# NNP-DWG-125-001-000_PG4_Schematic_Drawin.net
KiCad netlist of a schematic drawn in Altium Designer
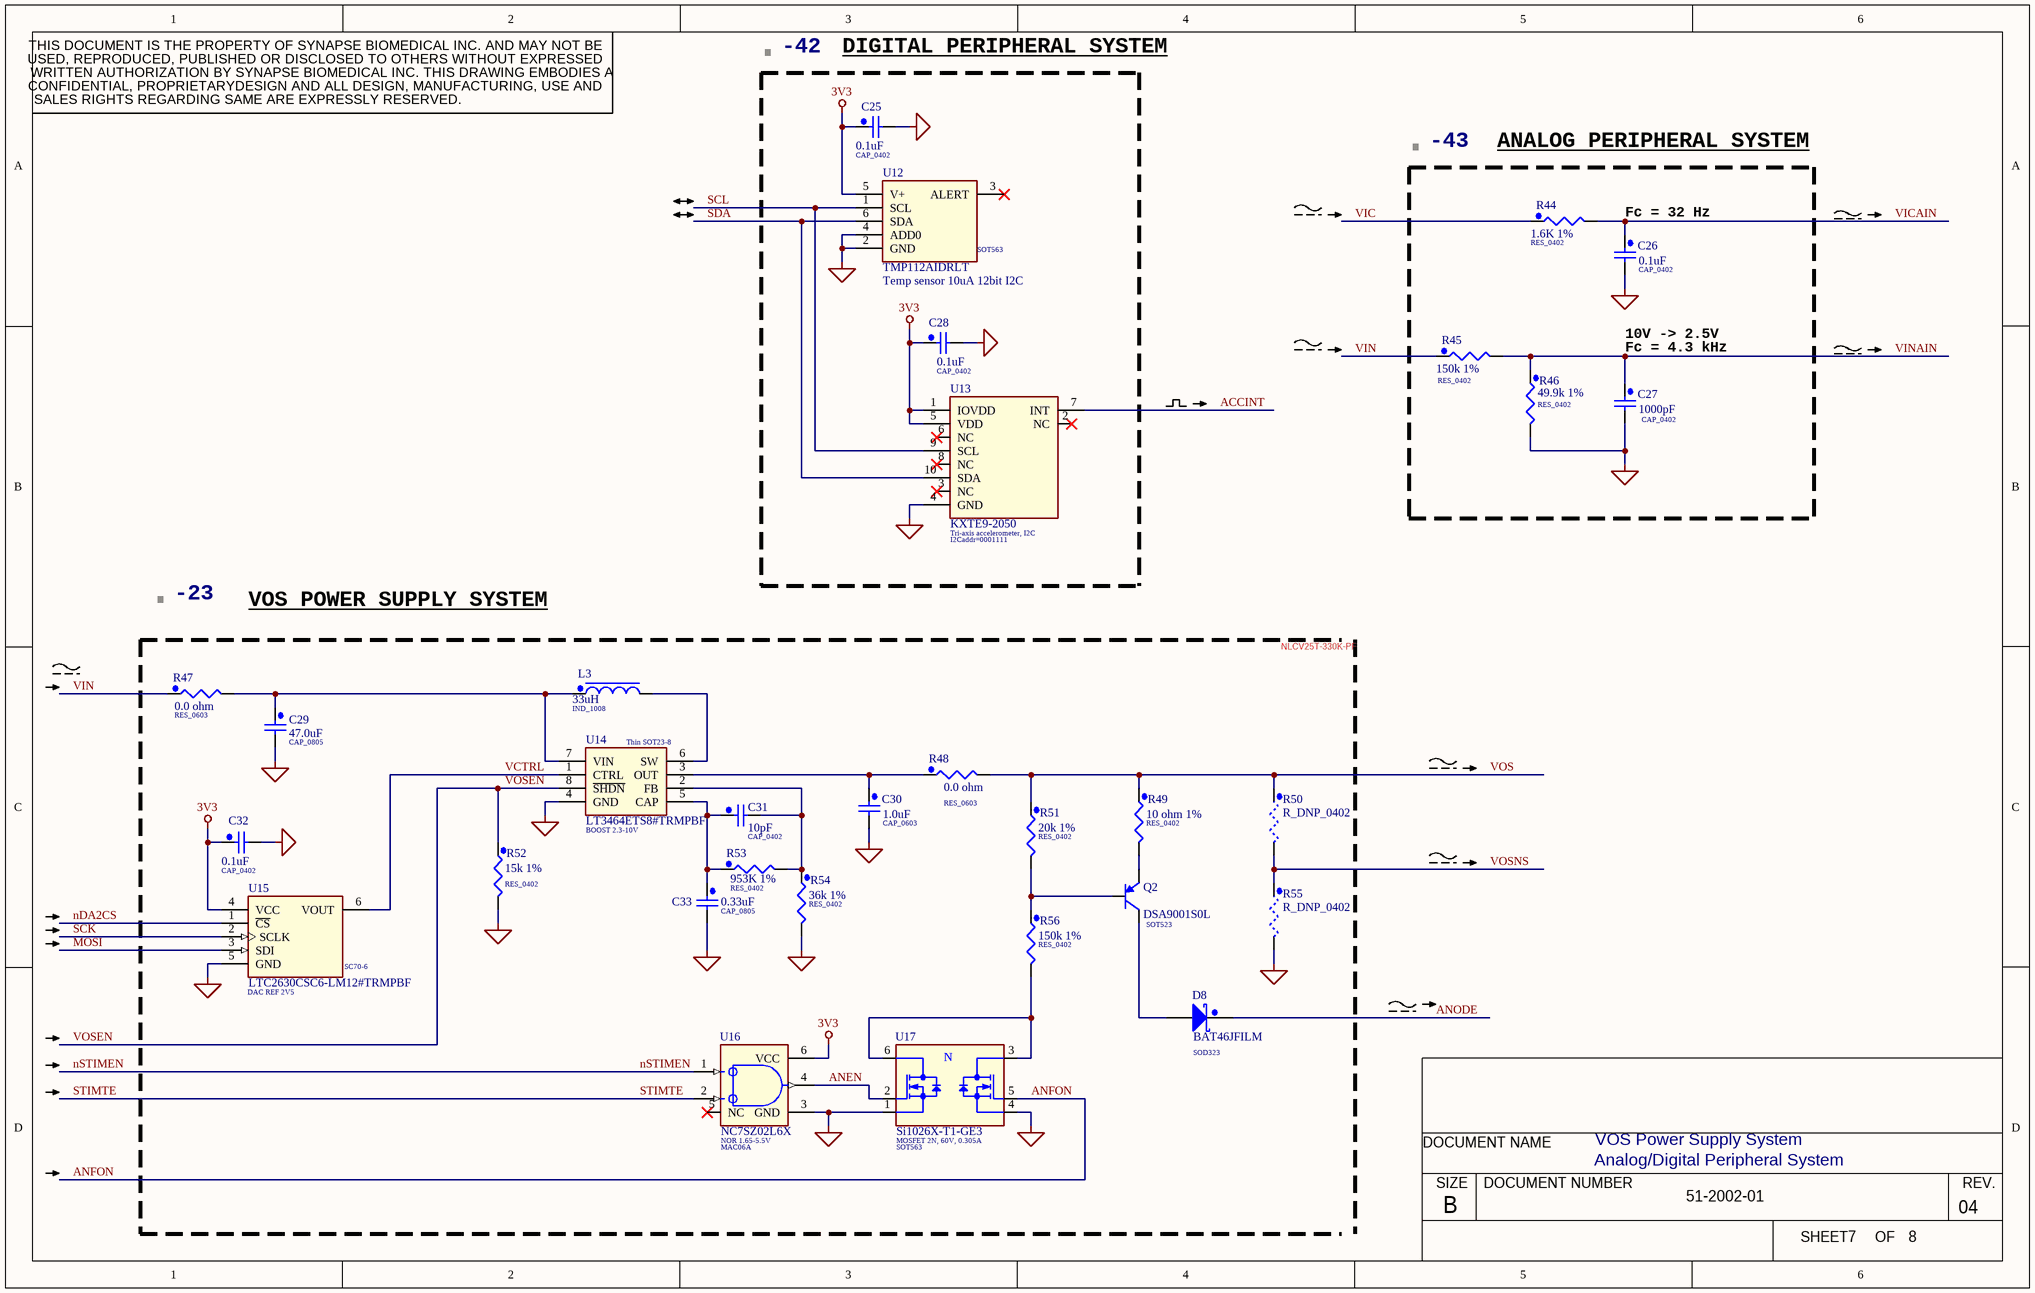
[diagram p0: NNP-DWG-125-001-000 PG4 Schematic Drawing Pg7.SchDoc]

(export (version "E")
  (design (tool "Eeschema 10.0.6"))
  (components
    (comp (ref "-23")
      (value "BOM_S1")
      (description "BOM item small graphic")
      (fields (field (name "XDESCRIPTION") "VOS POWER SUPPLY SYSTEM"))
      (libsource (lib "BOM_sym") (part "BOM_S1"))
    )
    (comp (ref "-42")
      (value "BOM_S1")
      (description "BOM item small graphic")
      (fields (field (name "XDESCRIPTION") "DIGITAL PERIPHERAL SYSTEM"))
      (libsource (lib "BOM_sym") (part "BOM_S1"))
    )
    (comp (ref "-43")
      (value "BOM_S1")
      (description "BOM item small graphic")
      (fields (field (name "XDESCRIPTION") "ANALOG PERIPHERAL SYSTEM"))
      (libsource (lib "BOM_sym") (part "BOM_S1"))
    )
    (comp (ref "C25")
      (value "0.1uF")
      (footprint "CAP_0402")
      (description "0.1uF, 16V, X7R, 0402, RoHS")
      (fields
        (field (name "MFR") "Murata Electronics North America")
        (field (name "PACKAGEDESCRIPTION") "CAP_0402")
        (field (name "MPN") "GRM155R71C104KA88D")
      )
      (libsource (lib "NNPS Integrated Parts") (part "GRM155R71C104KA88D"))
    )
    (comp (ref "C26")
      (value "0.1uF")
      (footprint "CAP_0402")
      (description "0.1uF, 16V, X7R, 0402, RoHS")
      (fields
        (field (name "MFR") "Murata Electronics North America")
        (field (name "PACKAGEDESCRIPTION") "CAP_0402")
        (field (name "MPN") "GRM155R71C104KA88D")
      )
      (libsource (lib "NNPS Integrated Parts") (part "GRM155R71C104KA88D"))
    )
    (comp (ref "C27")
      (value "1000pF")
      (footprint "CAP_0402")
      (description "1000pF, 50V, C0G, 5%, 0402, RoHS")
      (fields
        (field (name "MFR") "Murata Electronics North America")
        (field (name "PACKAGEDESCRIPTION") "CAP_0402")
        (field (name "MPN") "GRM1555C1H102JA01D")
      )
      (libsource (lib "NNPS Integrated Parts") (part "GRM1555C1H102JA01D"))
    )
    (comp (ref "C28")
      (value "0.1uF")
      (footprint "CAP_0402")
      (description "0.1uF, 16V, X7R, 0402, RoHS")
      (fields
        (field (name "MFR") "Murata Electronics North America")
        (field (name "PACKAGEDESCRIPTION") "CAP_0402")
        (field (name "MPN") "GRM155R71C104KA88D")
      )
      (libsource (lib "NNPS Integrated Parts") (part "GRM155R71C104KA88D"))
    )
    (comp (ref "C29")
      (value "47.0uF")
      (footprint "CAP_0805")
      (description "47uF, 10V, X5R, 20%, 0805, RoHS")
      (fields
        (field (name "MFR") "TDK Corporation")
        (field (name "PACKAGEDESCRIPTION") "CAP_0805")
        (field (name "MPN") "C2012X5R1A476M125AC")
      )
      (libsource (lib "NNPS Integrated Parts") (part "C2012X5R1A476M125AC"))
    )
    (comp (ref "C30")
      (value "1.0uF")
      (footprint "CAP_0603")
      (description "1uF, 50V, X5R, 10%, 0603, RoHS")
      (fields
        (field (name "MFR") "Murata Electronics North America")
        (field (name "PACKAGEDESCRIPTION") "CAP_0603")
        (field (name "MPN") "GRM188R61H105KAALD")
      )
      (libsource (lib "NNPS Integrated Parts") (part "UMK107BJ105KA-T"))
    )
    (comp (ref "C31")
      (value "10pF")
      (footprint "CAP_0402")
      (description "10pF, 50V, C0G, 5%, 0402, RoHS")
      (fields
        (field (name "MFR") "Murata Electronics North America")
        (field (name "PACKAGEDESCRIPTION") "CAP_0402")
        (field (name "MPN") "GRM1555C1H100JA01D")
      )
      (libsource (lib "NNPS Integrated Parts") (part "GRM1555C1H100JZ01"))
    )
    (comp (ref "C32")
      (value "0.1uF")
      (footprint "CAP_0402")
      (description "0.1uF, 16V, X7R, 0402, RoHS")
      (fields
        (field (name "MFR") "Murata Electronics North America")
        (field (name "PACKAGEDESCRIPTION") "CAP_0402")
        (field (name "MPN") "GRM155R71C104KA88D")
      )
      (libsource (lib "NNPS Integrated Parts") (part "GRM155R71C104KA88D"))
    )
    (comp (ref "C33")
      (value "0.33uF")
      (footprint "CAP_0805")
      (description "0.33uF, 50V, X7R, 10%, 0805, RoHS")
      (fields
        (field (name "MFR") "Murata Electronics North America")
        (field (name "PACKAGEDESCRIPTION") "CAP_0805")
        (field (name "MPN") "GRM216R71H331KA01D")
      )
      (libsource (lib "NNPS Integrated Parts") (part "GRM219R71H334KA88D"))
    )
    (comp (ref "D8")
      (value "BAT46JFILM")
      (footprint "SOD323")
      (description "Schottky Diode, 100V, 150mA, SOD323, RoHS")
      (fields
        (field (name "MFR") "STMicroelectronics")
        (field (name "PACKAGEDESCRIPTION") "SOD323")
        (field (name "Comment") "D_100_150m_SOD323")
      )
      (libsource (lib "NNPS Integrated Parts") (part "BAT46JFILM"))
    )
    (comp (ref "L3")
      (value "33uH")
      (footprint "IND_1008")
      (description "33uH, 120mA, 10%, RoHS")
      (fields
        (field (name "MFR") "TDK Corporation")
        (field (name "PACKAGEDESCRIPTION") "IND_1008")
        (field (name "MPN") "NLCV25T-330K-PF")
      )
      (libsource (lib "NNPS Integrated Parts") (part "ELJ-PC330KF"))
    )
    (comp (ref "Q2")
      (value "Q_-50_-100m_SOT523")
      (footprint "SOT523")
      (description "PNP, -50V, -100mA, SOT523, 150MHz, RoHS")
      (fields
        (field (name "PACKAGEDESCRIPTION") "SOT523")
        (field (name "MFR") "Panasonic Electronic Components")
        (field (name "MPN") "DSA9001S0L")
      )
      (libsource (lib "NNPS Integrated Parts") (part "DSA9001"))
    )
    (comp (ref "R44")
      (value "1.6K 1%")
      (footprint "RES_0402")
      (description "1.6K ohm, 1%, 1/16W, smd, 0402, RoHS")
      (fields
        (field (name "MFR") "Vishay")
        (field (name "PACKAGEDESCRIPTION") "RES_0402")
        (field (name "MPN") "CRCW04021K60FKED")
      )
      (libsource (lib "NNPS Integrated Parts") (part "CRCW04021K60FKED"))
    )
    (comp (ref "R45")
      (value "150k 1%")
      (footprint "RES_0402")
      (description "150k ohm, 1%, 1/16W, smd, 0402, RoHS")
      (fields
        (field (name "MFR") "Vishay Dale")
        (field (name "PACKAGEDESCRIPTION") "RES_0402")
        (field (name "MPN") "CRCW0402150KFKED")
      )
      (libsource (lib "NNPS Integrated Parts") (part "MCR01MZPF1503"))
    )
    (comp (ref "R46")
      (value "49.9k 1%")
      (footprint "RES_0402")
      (description "49.9k ohm, 1%, 1/16W, 0402, RoHS")
      (fields
        (field (name "MFR") "Vishay Dale")
        (field (name "PACKAGEDESCRIPTION") "RES_0402")
        (field (name "MPN") "CRCW040249K9FKED")
      )
      (libsource (lib "NNPS Integrated Parts") (part "MCR01MZPF4992"))
    )
    (comp (ref "R47")
      (value "0.0 ohm")
      (footprint "RES_0603")
      (description "0.0 ohm, 1/10W, 0603, RoHS")
      (fields
        (field (name "MFR") "Vishay Dale")
        (field (name "PACKAGEDESCRIPTION") "RES_0603")
        (field (name "MPN") "MCR03ERTJ000")
      )
      (libsource (lib "NNPS Integrated Parts") (part "MCR03ERTJ000"))
    )
    (comp (ref "R48")
      (value "0.0 ohm")
      (footprint "RES_0603")
      (description "0.0 ohm, 1/10W, 0603, RoHS")
      (fields
        (field (name "MFR") "Vishay Dale")
        (field (name "PACKAGEDESCRIPTION") "RES_0603")
        (field (name "MPN") "MCR03ERTJ000")
      )
      (libsource (lib "NNPS Integrated Parts") (part "MCR03ERTJ000"))
    )
    (comp (ref "R49")
      (value "10 ohm 1%")
      (footprint "RES_0402")
      (description "10 ohm, 1%, 1/16W, 0402, RoHS")
      (fields
        (field (name "MFR") "Vishay Dale")
        (field (name "PACKAGEDESCRIPTION") "RES_0402")
        (field (name "MPN") "CRCW040210R0FKED")
      )
      (libsource (lib "NNPS Integrated Parts") (part "MCR01MZPF10R0"))
    )
    (comp (ref "R50")
      (value "R_DNP_0402")
      (footprint "RES_0402")
      (description "0.0 ohm 1/16W smd 0402 RoHS")
      (fields (field (name "MFR") "DO NOT POPULATE"))
      (libsource (lib "NNPS Integrated Parts") (part "R_DNP_0402"))
    )
    (comp (ref "R51")
      (value "20k 1%")
      (footprint "RES_0402")
      (description "20k ohm, 1%, 1/16W, 0402, RoHS")
      (fields
        (field (name "MFR") "Vishay Dale")
        (field (name "PACKAGEDESCRIPTION") "RES_0402")
        (field (name "MPN") "CRCW040220K0FKED")
      )
      (libsource (lib "NNPS Integrated Parts") (part "MCR01MZPF2002"))
    )
    (comp (ref "R52")
      (value "15k 1%")
      (footprint "RES_0402")
      (description "15.0k ohm, 1%, 1/16W, smd, 0402, RoHS")
      (fields
        (field (name "MFR") "Vishay Dale")
        (field (name "PACKAGEDESCRIPTION") "RES_0402")
        (field (name "MPN") "CRCW040215K0FKED")
      )
      (libsource (lib "NNPS Integrated Parts") (part "MCR01MZPF1502"))
    )
    (comp (ref "R53")
      (value "953K 1%")
      (footprint "RES_0402")
      (description "953k ohm, 1%, 1/16W, 0402, RoHS")
      (fields
        (field (name "MFR") "Vishay Dale")
        (field (name "PACKAGEDESCRIPTION") "RES_0402")
        (field (name "MPN") "CRCW0402953KFKED")
      )
      (libsource (lib "NNPS Integrated Parts") (part "CRCW0402953KFKED"))
    )
    (comp (ref "R54")
      (value "36k 1%")
      (footprint "RES_0402")
      (description "36k ohm , 1%, 1/16W, 0402, RoHS")
      (fields
        (field (name "MFR") "Vishay Dale")
        (field (name "PACKAGEDESCRIPTION") "RES_0402")
        (field (name "MPN") "CRCW040236K0FKED")
      )
      (libsource (lib "NNPS Integrated Parts") (part "MCR01MZPF3602"))
    )
    (comp (ref "R55")
      (value "R_DNP_0402")
      (footprint "RES_0402")
      (description "0.0 ohm 1/16W smd 0402 RoHS")
      (fields (field (name "MFR") "DO NOT POPULATE"))
      (libsource (lib "NNPS Integrated Parts") (part "R_DNP_0402"))
    )
    (comp (ref "R56")
      (value "150k 1%")
      (footprint "RES_0402")
      (description "150k ohm, 1%, 1/16W, smd, 0402, RoHS")
      (fields
        (field (name "MFR") "Vishay Dale")
        (field (name "PACKAGEDESCRIPTION") "RES_0402")
        (field (name "MPN") "CRCW0402150KFKED")
      )
      (libsource (lib "NNPS Integrated Parts") (part "MCR01MZPF1503"))
    )
    (comp (ref "U12")
      (value "Temp sensor 10uA 12bit I2C")
      (footprint "SOT-563")
      (description "Temperature Sensor,12bit I2C,  SOT563, RoHS")
      (fields
        (field (name "MFR") "Texas Instruments")
        (field (name "PACKAGEDESCRIPTION") "SOT563")
        (field (name "MPN") "TMP112AIDRLT")
      )
      (libsource (lib "NNPS Integrated Parts") (part "TMP112AIDRLT"))
    )
    (comp (ref "U13")
      (value "Tri-axis accelerometer, I2C")
      (footprint "LGA10")
      (description "Tri-axis accelerometer, I2C,  LGA10, RoHS")
      (fields
        (field (name "MFR") "Kionix")
        (field (name "NOTE") "I2Caddr=0001111")
        (field (name "MPN") "KXTE9-2050")
      )
      (libsource (lib "NNPS Integrated Parts") (part "KXTE9-2050"))
    )
    (comp (ref "U14")
      (value "BOOST 2.3-10V")
      (footprint "SOT23-8")
      (description "BOOST, 2.3-10V, TSOT23-8, RoHS")
      (fields
        (field (name "PACKAGEDESCRIPTION") "Thin SOT23-8")
        (field (name "MFR") "Linear Technology")
        (field (name "MPN") "LT3464ETS8#TRMPBF")
      )
      (libsource (lib "NNPS Integrated Parts") (part "LT3464ETS8"))
    )
    (comp (ref "U15")
      (value "DAC REF 2V5")
      (footprint "SC70-6")
      (description "DAC 2V5 internal reference, RoHS")
      (fields
        (field (name "PACKAGEDESCRIPTION") "SC70-6")
        (field (name "MFR") "Linear Technology")
        (field (name "MPN") "LTC2630CSC6-LM12#TRMPBF")
      )
      (libsource (lib "NNPS Integrated Parts") (part "LTC2630-LM12"))
    )
    (comp (ref "U16")
      (value "NOR 1.65-5.5V")
      (footprint "uPak6")
      (description "2-Input NOR, 1.65-5.5V, uPak6, RoHS")
      (fields
        (field (name "MFR") "Fairchild Semiconductor")
        (field (name "PACKAGEDESCRIPTION") "MAC06A")
        (field (name "MPN") "NC7SZ02L6X")
      )
      (libsource (lib "NNPS Integrated Parts") (part "NC7SZ02L6X"))
    )
    (comp (ref "U17")
      (value "MOSFET 2N, 60V, 0.305A")
      (footprint "SOT-563")
      (description "MOSFET 2N, 60V, 0.305A, RoHS")
      (fields
        (field (name "MFR") "Vishay Siliconix")
        (field (name "PACKAGEDESCRIPTION") "SOT563")
        (field (name "MPN") "Si1026X-T1-GE3")
      )
      (libsource (lib "NNPS Integrated Parts") (part "Si1026X-T1-E3"))
    )
  )
  (nets
    (net (code "1") (name "/ACCINT") (class "Default")
      (node (ref "U13") (pin "7") (pinfunction "INT_7") (pintype "passive"))
    )
    (net (code "2") (name "/ANEN") (class "Default")
      (node (ref "U16") (pin "4") (pinfunction "Y_4") (pintype "output"))
      (node (ref "U17") (pin "2") (pinfunction "G1_2") (pintype "passive"))
    )
    (net (code "3") (name "/ANFON") (class "Default")
      (node (ref "U17") (pin "5") (pinfunction "G2_5") (pintype "passive"))
    )
    (net (code "4") (name "/ANODE") (class "Default")
      (node (ref "D8") (pin "1") (pinfunction "C_1") (pintype "passive"))
    )
    (net (code "5") (name "/MOSI") (class "Default")
      (node (ref "U15") (pin "3") (pinfunction "SDI_3") (pintype "input"))
    )
    (net (code "6") (name "/SCK") (class "Default")
      (node (ref "U15") (pin "2") (pinfunction "SCLK_2") (pintype "input"))
    )
    (net (code "7") (name "/SCL") (class "Default")
      (node (ref "U12") (pin "1") (pinfunction "SCL_1") (pintype "passive"))
      (node (ref "U13") (pin "9") (pinfunction "SCL_9") (pintype "passive"))
    )
    (net (code "8") (name "/SDA") (class "Default")
      (node (ref "U12") (pin "6") (pinfunction "SDA_6") (pintype "passive"))
      (node (ref "U13") (pin "10") (pinfunction "SDA_10") (pintype "passive"))
    )
    (net (code "9") (name "/STIMTE") (class "Default")
      (node (ref "U16") (pin "2") (pinfunction "B_2") (pintype "input"))
    )
    (net (code "10") (name "/VCTRL") (class "Default")
      (node (ref "U14") (pin "1") (pinfunction "CTRL_1") (pintype "passive"))
      (node (ref "U15") (pin "6") (pinfunction "VOUT_6") (pintype "passive"))
    )
    (net (code "11") (name "/VIC") (class "Default")
      (node (ref "R44") (pin "1") (pinfunction "1_1") (pintype "passive"))
    )
    (net (code "12") (name "/VICAIN") (class "Default")
      (node (ref "C26") (pin "1") (pinfunction "1_1") (pintype "passive"))
      (node (ref "R44") (pin "2") (pinfunction "2_2") (pintype "passive"))
    )
    (net (code "13") (name "/VIN") (class "Default")
      (node (ref "R45") (pin "1") (pinfunction "1_1") (pintype "passive"))
      (node (ref "R47") (pin "1") (pinfunction "1_1") (pintype "passive"))
    )
    (net (code "14") (name "/VINAIN") (class "Default")
      (node (ref "C27") (pin "1") (pinfunction "1_1") (pintype "passive"))
      (node (ref "R45") (pin "2") (pinfunction "2_2") (pintype "passive"))
      (node (ref "R46") (pin "1") (pinfunction "1_1") (pintype "passive"))
    )
    (net (code "15") (name "/VOS") (class "Default")
      (node (ref "R48") (pin "2") (pinfunction "2_2") (pintype "passive"))
      (node (ref "R49") (pin "1") (pinfunction "1_1") (pintype "passive"))
      (node (ref "R50") (pin "1") (pinfunction "1_1") (pintype "passive"))
      (node (ref "R51") (pin "1") (pinfunction "1_1") (pintype "passive"))
    )
    (net (code "16") (name "/VOSEN") (class "Default")
      (node (ref "R52") (pin "1") (pinfunction "1_1") (pintype "passive"))
      (node (ref "U14") (pin "8") (pinfunction "~{SHDN}_8") (pintype "passive"))
    )
    (net (code "17") (name "/VOSNS") (class "Default")
      (node (ref "R50") (pin "2") (pinfunction "2_2") (pintype "passive"))
      (node (ref "R55") (pin "1") (pinfunction "1_1") (pintype "passive"))
    )
    (net (code "18") (name "/nDA2CS") (class "Default")
      (node (ref "U15") (pin "1") (pinfunction "CS_1") (pintype "passive"))
    )
    (net (code "19") (name "/nSTIMEN") (class "Default")
      (node (ref "U16") (pin "1") (pinfunction "A_1") (pintype "input"))
    )
    (net (code "20") (name "3V3") (class "Default")
      (node (ref "C25") (pin "1") (pinfunction "1_1") (pintype "passive"))
      (node (ref "C28") (pin "1") (pinfunction "1_1") (pintype "passive"))
      (node (ref "C32") (pin "1") (pinfunction "1_1") (pintype "passive"))
      (node (ref "U12") (pin "5") (pinfunction "V+_5") (pintype "power_in"))
      (node (ref "U13") (pin "1") (pinfunction "IOVDD_1") (pintype "passive"))
      (node (ref "U13") (pin "5") (pinfunction "VDD_5") (pintype "passive"))
      (node (ref "U15") (pin "4") (pinfunction "VCC_4") (pintype "power_in"))
      (node (ref "U16") (pin "6") (pinfunction "VCC_6") (pintype "power_in"))
    )
    (net (code "21") (name "GND") (class "Default")
      (node (ref "C25") (pin "2") (pinfunction "2_2") (pintype "passive"))
      (node (ref "C26") (pin "2") (pinfunction "2_2") (pintype "passive"))
      (node (ref "C27") (pin "2") (pinfunction "2_2") (pintype "passive"))
      (node (ref "C28") (pin "2") (pinfunction "2_2") (pintype "passive"))
      (node (ref "C29") (pin "2") (pinfunction "2_2") (pintype "passive"))
      (node (ref "C30") (pin "2") (pinfunction "2_2") (pintype "passive"))
      (node (ref "C32") (pin "2") (pinfunction "2_2") (pintype "passive"))
      (node (ref "C33") (pin "2") (pinfunction "2_2") (pintype "passive"))
      (node (ref "R46") (pin "2") (pinfunction "2_2") (pintype "passive"))
      (node (ref "R52") (pin "2") (pinfunction "2_2") (pintype "passive"))
      (node (ref "R54") (pin "2") (pinfunction "2_2") (pintype "passive"))
      (node (ref "R55") (pin "2") (pinfunction "2_2") (pintype "passive"))
      (node (ref "U12") (pin "2") (pinfunction "GND_2") (pintype "power_in"))
      (node (ref "U12") (pin "4") (pinfunction "ADD0_4") (pintype "passive"))
      (node (ref "U13") (pin "4") (pinfunction "GND_4") (pintype "passive"))
      (node (ref "U14") (pin "4") (pinfunction "GND_4") (pintype "passive"))
      (node (ref "U15") (pin "5") (pinfunction "GND_5") (pintype "power_in"))
      (node (ref "U16") (pin "3") (pinfunction "GND_3") (pintype "power_in"))
      (node (ref "U17") (pin "1") (pinfunction "S1_1") (pintype "passive"))
      (node (ref "U17") (pin "4") (pinfunction "S2_4") (pintype "passive"))
    )
    (net (code "22") (name "Net-(D8-A)") (class "Default")
      (node (ref "D8") (pin "2") (pinfunction "A_2") (pintype "passive"))
      (node (ref "Q2") (pin "3") (pinfunction "C_3") (pintype "passive"))
    )
    (net (code "23") (name "Net-(Q2-B)") (class "Default")
      (node (ref "Q2") (pin "1") (pinfunction "B_1") (pintype "passive"))
      (node (ref "R51") (pin "2") (pinfunction "2_2") (pintype "passive"))
      (node (ref "R56") (pin "1") (pinfunction "1_1") (pintype "passive"))
    )
    (net (code "24") (name "Net-(Q2-E)") (class "Default")
      (node (ref "Q2") (pin "2") (pinfunction "E_2") (pintype "passive"))
      (node (ref "R49") (pin "2") (pinfunction "2_2") (pintype "passive"))
    )
    (net (code "25") (name "Net-(U14-CAP)") (class "Default")
      (node (ref "C31") (pin "1") (pinfunction "1_1") (pintype "passive"))
      (node (ref "C33") (pin "1") (pinfunction "1_1") (pintype "passive"))
      (node (ref "R53") (pin "1") (pinfunction "1_1") (pintype "passive"))
      (node (ref "U14") (pin "5") (pinfunction "CAP_5") (pintype "passive"))
    )
    (net (code "26") (name "Net-(U14-FB)") (class "Default")
      (node (ref "C31") (pin "2") (pinfunction "2_2") (pintype "passive"))
      (node (ref "R53") (pin "2") (pinfunction "2_2") (pintype "passive"))
      (node (ref "R54") (pin "1") (pinfunction "1_1") (pintype "passive"))
      (node (ref "U14") (pin "2") (pinfunction "FB_2") (pintype "passive"))
    )
    (net (code "27") (name "Net-(U14-OUT)") (class "Default")
      (node (ref "C30") (pin "1") (pinfunction "1_1") (pintype "passive"))
      (node (ref "R48") (pin "1") (pinfunction "1_1") (pintype "passive"))
      (node (ref "U14") (pin "3") (pinfunction "OUT_3") (pintype "passive"))
    )
    (net (code "28") (name "Net-(U14-SW)") (class "Default")
      (node (ref "L3") (pin "2") (pinfunction "2_2") (pintype "passive"))
      (node (ref "U14") (pin "6") (pinfunction "SW_6") (pintype "passive"))
    )
    (net (code "29") (name "Net-(U14-VIN)") (class "Default")
      (node (ref "C29") (pin "1") (pinfunction "1_1") (pintype "passive"))
      (node (ref "L3") (pin "1") (pinfunction "1_1") (pintype "passive"))
      (node (ref "R47") (pin "2") (pinfunction "2_2") (pintype "passive"))
      (node (ref "U14") (pin "7") (pinfunction "VIN_7") (pintype "passive"))
    )
    (net (code "30") (name "Net-(U17-D1)") (class "Default")
      (node (ref "R56") (pin "2") (pinfunction "2_2") (pintype "passive"))
      (node (ref "U17") (pin "3") (pinfunction "D2_3") (pintype "passive"))
      (node (ref "U17") (pin "6") (pinfunction "D1_6") (pintype "passive"))
    )
    (net (code "31") (name "unconnected-(U12-ALERT-Pad3)") (class "Default")
      (node (ref "U12") (pin "3") (pinfunction "ALERT_3") (pintype "passive+no_connect"))
    )
    (net (code "32") (name "unconnected-(U13-NC-Pad2)") (class "Default")
      (node (ref "U13") (pin "2") (pinfunction "NC_2") (pintype "power_in+no_connect"))
    )
    (net (code "33") (name "unconnected-(U13-NC-Pad3)") (class "Default")
      (node (ref "U13") (pin "3") (pinfunction "NC_3") (pintype "passive+no_connect"))
    )
    (net (code "34") (name "unconnected-(U13-NC-Pad6)") (class "Default")
      (node (ref "U13") (pin "6") (pinfunction "NC_6") (pintype "passive+no_connect"))
    )
    (net (code "35") (name "unconnected-(U13-NC-Pad8)") (class "Default")
      (node (ref "U13") (pin "8") (pinfunction "NC_8") (pintype "passive+no_connect"))
    )
    (net (code "36") (name "unconnected-(U16-NC-Pad5)") (class "Default")
      (node (ref "U16") (pin "5") (pinfunction "NC_5") (pintype "passive+no_connect"))
    )
  )
)
